# Gambar_Teknik_Raihansyah_Akbar_M__215073.net
KiCad netlist of a schematic drawn in EAGLE
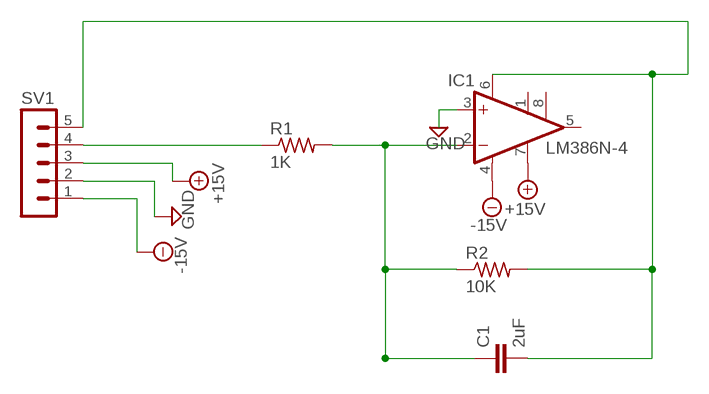
[diagram p0: schematic, sheet 1]

(export (version "E")
  (design (tool "Eeschema 10.0.6"))
  (components
    (comp (ref "C1")
      (value "2uF")
      (footprint "eagle-import:C025-024X044")
      (libsource (lib "eagle-import") (part "C-EU025-024X044"))
    )
    (comp (ref "IC1")
      (value "LM386N-4")
      (footprint "eagle-import:DIL08")
      (libsource (lib "eagle-import") (part "LM386?-N4"))
    )
    (comp (ref "R1")
      (value "1K")
      (footprint "eagle-import:V526-0")
      (libsource (lib "eagle-import") (part "R-US_V526-0"))
    )
    (comp (ref "R2")
      (value "10K")
      (footprint "eagle-import:V526-0")
      (libsource (lib "eagle-import") (part "R-US_V526-0"))
    )
    (comp (ref "SV1")
      (value "MA05-1")
      (footprint "eagle-import:MA05-1")
      (libsource (lib "eagle-import") (part "MA05-1"))
    )
  )
  (nets
    (net (code "1") (name "+15V") (class "Default")
      (node (ref "IC1") (pin "7") (pinfunction "BYPASS_7") (pintype "passive"))
      (node (ref "SV1") (pin "3") (pinfunction "3_3") (pintype "passive"))
    )
    (net (code "2") (name "-15V") (class "Default")
      (node (ref "IC1") (pin "4") (pinfunction "GND_4") (pintype "power_in"))
      (node (ref "SV1") (pin "1") (pinfunction "1_1") (pintype "passive"))
    )
    (net (code "3") (name "GND") (class "Default")
      (node (ref "IC1") (pin "3") (pinfunction "+IN_3") (pintype "input"))
      (node (ref "SV1") (pin "2") (pinfunction "2_2") (pintype "passive"))
    )
    (net (code "4") (name "Net-(IC1--IN)") (class "Default")
      (node (ref "C1") (pin "1") (pinfunction "1_1") (pintype "passive"))
      (node (ref "IC1") (pin "2") (pinfunction "-IN_2") (pintype "input"))
      (node (ref "R1") (pin "2") (pinfunction "2_2") (pintype "passive"))
      (node (ref "R2") (pin "1") (pinfunction "1_1") (pintype "passive"))
    )
    (net (code "5") (name "Net-(IC1-VS)") (class "Default")
      (node (ref "C1") (pin "2") (pinfunction "2_2") (pintype "passive"))
      (node (ref "IC1") (pin "6") (pinfunction "VS_6") (pintype "power_in"))
      (node (ref "R2") (pin "2") (pinfunction "2_2") (pintype "passive"))
      (node (ref "SV1") (pin "5") (pinfunction "5_5") (pintype "passive"))
    )
    (net (code "6") (name "Net-(R1-Pad1)") (class "Default")
      (node (ref "R1") (pin "1") (pinfunction "1_1") (pintype "passive"))
      (node (ref "SV1") (pin "4") (pinfunction "4_4") (pintype "passive"))
    )
    (net (code "7") (name "unconnected-(IC1-GAIN-Pad1)") (class "Default")
      (node (ref "IC1") (pin "1") (pinfunction "GAIN_1") (pintype "passive"))
    )
    (net (code "8") (name "unconnected-(IC1-GAIN-Pad8)") (class "Default")
      (node (ref "IC1") (pin "8") (pinfunction "GAIN_8") (pintype "passive"))
    )
    (net (code "9") (name "unconnected-(IC1-OUT-Pad5)") (class "Default")
      (node (ref "IC1") (pin "5") (pinfunction "OUT_5") (pintype "output"))
    )
  )
)
